# xbox360_charger.net
KiCad netlist of a schematic drawn in EAGLE
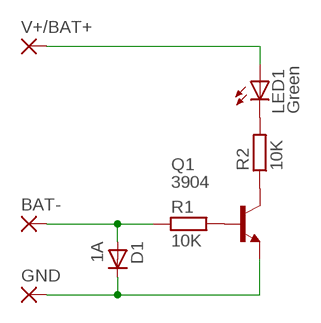
[diagram p0: schematic, sheet 1]

(export (version "E")
  (design (tool "Eeschema 10.0.6"))
  (components
    (comp (ref "BAT-")
      (value "SMD5")
      (footprint "eagle-import:SMD2,54-5,08")
      (libsource (lib "eagle-import") (part "SMD5"))
    )
    (comp (ref "D1")
      (value "1A")
      (footprint "eagle-import:DIOM5436X265N")
      (libsource (lib "eagle-import") (part "DIODE_SMB"))
    )
    (comp (ref "GND")
      (value "SMD5")
      (footprint "eagle-import:SMD2,54-5,08")
      (libsource (lib "eagle-import") (part "SMD5"))
    )
    (comp (ref "LED1")
      (value "Green")
      (footprint "eagle-import:SML0603")
      (libsource (lib "eagle-import") (part "LEDSML0603"))
    )
    (comp (ref "Q1")
      (value "3904")
      (footprint "eagle-import:SOT95P280X135-3N")
      (libsource (lib "eagle-import") (part "NPN_SOT-23"))
    )
    (comp (ref "R1")
      (value "10K")
      (footprint "eagle-import:RESC1608X55N")
      (libsource (lib "eagle-import") (part "RESISTOR_0603"))
    )
    (comp (ref "R2")
      (value "10K")
      (footprint "eagle-import:RESC1608X55N")
      (libsource (lib "eagle-import") (part "RESISTOR_0603"))
    )
    (comp (ref "V+/BAT+")
      (value "SMD5")
      (footprint "eagle-import:SMD2,54-5,08")
      (libsource (lib "eagle-import") (part "SMD5"))
    )
  )
  (nets
    (net (code "1") (name "Net-(BAT--P)") (class "Default")
      (node (ref "BAT-") (pin "1") (pinfunction "P_1") (pintype "passive"))
      (node (ref "D1") (pin "A") (pinfunction "A_A") (pintype "passive"))
      (node (ref "R1") (pin "1") (pinfunction "1_1") (pintype "passive"))
    )
    (net (code "2") (name "Net-(GND-P)") (class "Default")
      (node (ref "D1") (pin "K") (pinfunction "K_K") (pintype "passive"))
      (node (ref "GND") (pin "1") (pinfunction "P_1") (pintype "passive"))
      (node (ref "Q1") (pin "2") (pinfunction "E_2") (pintype "passive"))
    )
    (net (code "3") (name "Net-(LED1-PadC)") (class "Default")
      (node (ref "LED1") (pin "C") (pinfunction "C_C") (pintype "passive"))
      (node (ref "R2") (pin "2") (pinfunction "2_2") (pintype "passive"))
    )
    (net (code "4") (name "Net-(Q1-B)") (class "Default")
      (node (ref "Q1") (pin "1") (pinfunction "B_1") (pintype "passive"))
      (node (ref "R1") (pin "2") (pinfunction "2_2") (pintype "passive"))
    )
    (net (code "5") (name "Net-(Q1-C)") (class "Default")
      (node (ref "Q1") (pin "3") (pinfunction "C_3") (pintype "passive"))
      (node (ref "R2") (pin "1") (pinfunction "1_1") (pintype "passive"))
    )
    (net (code "6") (name "Net-(V+/BAT+-P)") (class "Default")
      (node (ref "LED1") (pin "A") (pinfunction "A_A") (pintype "passive"))
      (node (ref "V+/BAT+") (pin "1") (pinfunction "P_1") (pintype "passive"))
    )
  )
)
